# cs3_redraw.net
KiCad netlist of a schematic drawn in EAGLE
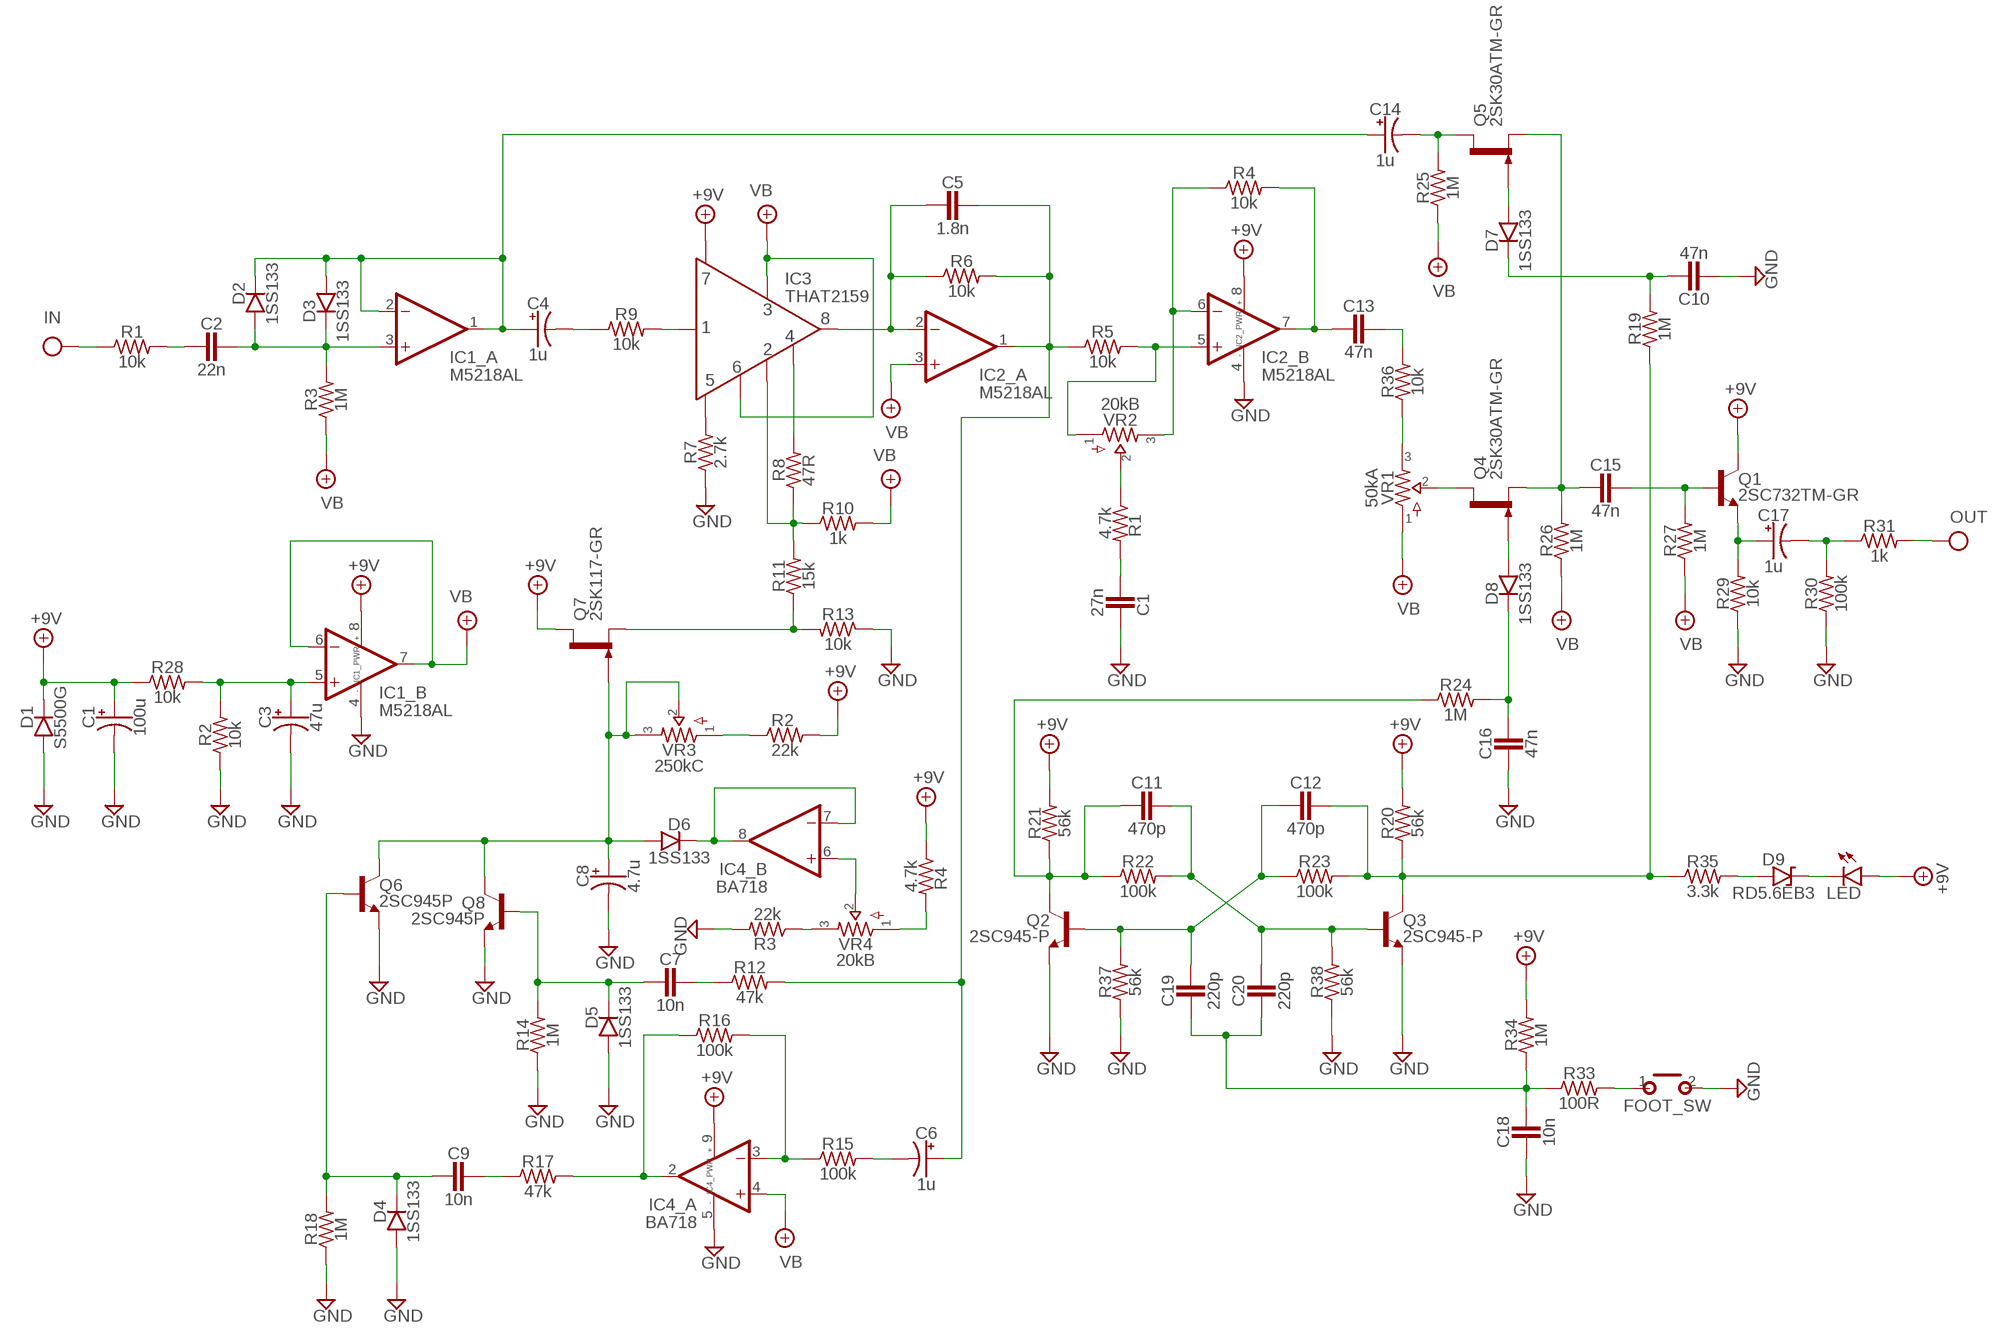
[diagram p0: schematic, sheet 1]

(export (version "E")
  (design (tool "Eeschema 10.0.6"))
  (components
    (comp (ref "C1")
      (value "100u")
      (footprint "eagle-import:040_020")
      (libsource (lib "eagle-import") (part "0400"))
    )
    (comp (ref "C1 ")
      (value "27n")
      (footprint "eagle-import:BOX_SMALL")
      (libsource (lib "eagle-import") (part "CER/FILMBOX.1"))
    )
    (comp (ref "C2")
      (value "22n")
      (footprint "eagle-import:BOX_SMALL")
      (libsource (lib "eagle-import") (part "CER/FILMBOX.1"))
    )
    (comp (ref "C3")
      (value "47u")
      (footprint "eagle-import:040_020")
      (libsource (lib "eagle-import") (part "0400"))
    )
    (comp (ref "C4")
      (value "1u")
      (footprint "eagle-import:040_020")
      (libsource (lib "eagle-import") (part "0400"))
    )
    (comp (ref "C5")
      (value "1.8n")
      (footprint "eagle-import:BOX_SMALL")
      (libsource (lib "eagle-import") (part "CER/FILMBOX.1"))
    )
    (comp (ref "C6")
      (value "1u")
      (footprint "eagle-import:040_020")
      (libsource (lib "eagle-import") (part "0400"))
    )
    (comp (ref "C7")
      (value "10n")
      (footprint "eagle-import:BOX_SMALL")
      (libsource (lib "eagle-import") (part "CER/FILMBOX.1"))
    )
    (comp (ref "C8")
      (value "4.7u")
      (footprint "eagle-import:040_020")
      (libsource (lib "eagle-import") (part "0400"))
    )
    (comp (ref "C9")
      (value "10n")
      (footprint "eagle-import:BOX_SMALL")
      (libsource (lib "eagle-import") (part "CER/FILMBOX.1"))
    )
    (comp (ref "C10")
      (value "47n")
      (footprint "eagle-import:BOX_SMALL")
      (libsource (lib "eagle-import") (part "CER/FILMBOX.1"))
    )
    (comp (ref "C11")
      (value "470p")
      (footprint "eagle-import:BOX_SMALL")
      (libsource (lib "eagle-import") (part "CER/FILMBOX.1"))
    )
    (comp (ref "C12")
      (value "470p")
      (footprint "eagle-import:BOX_SMALL")
      (libsource (lib "eagle-import") (part "CER/FILMBOX.1"))
    )
    (comp (ref "C13")
      (value "47n")
      (footprint "eagle-import:BOX_SMALL")
      (libsource (lib "eagle-import") (part "CER/FILMBOX.1"))
    )
    (comp (ref "C14")
      (value "1u")
      (footprint "eagle-import:040_020")
      (libsource (lib "eagle-import") (part "0400"))
    )
    (comp (ref "C15")
      (value "47n")
      (footprint "eagle-import:BOX_SMALL")
      (libsource (lib "eagle-import") (part "CER/FILMBOX.1"))
    )
    (comp (ref "C16")
      (value "47n")
      (footprint "eagle-import:BOX_SMALL")
      (libsource (lib "eagle-import") (part "CER/FILMBOX.1"))
    )
    (comp (ref "C17")
      (value "1u")
      (footprint "eagle-import:040_020")
      (libsource (lib "eagle-import") (part "0400"))
    )
    (comp (ref "C18")
      (value "10n")
      (footprint "eagle-import:BOX_SMALL")
      (libsource (lib "eagle-import") (part "CER/FILMBOX.1"))
    )
    (comp (ref "C19")
      (value "220p")
      (footprint "eagle-import:BOX_SMALL")
      (libsource (lib "eagle-import") (part "CER/FILMBOX.1"))
    )
    (comp (ref "C20")
      (value "220p")
      (footprint "eagle-import:BOX_SMALL")
      (libsource (lib "eagle-import") (part "CER/FILMBOX.1"))
    )
    (comp (ref "D1")
      (value "S5500G")
      (footprint "eagle-import:DO35-2")
      (libsource (lib "eagle-import") (part "DO35.2"))
    )
    (comp (ref "D2")
      (value "1SS133")
      (footprint "eagle-import:DO35-2")
      (libsource (lib "eagle-import") (part "DO35.2"))
    )
    (comp (ref "D3")
      (value "1SS133")
      (footprint "eagle-import:DO35-2")
      (libsource (lib "eagle-import") (part "DO35.2"))
    )
    (comp (ref "D4")
      (value "1SS133")
      (footprint "eagle-import:DO35-2")
      (libsource (lib "eagle-import") (part "DO35.2"))
    )
    (comp (ref "D5")
      (value "1SS133")
      (footprint "eagle-import:DO35-2")
      (libsource (lib "eagle-import") (part "DO35.2"))
    )
    (comp (ref "D6")
      (value "1SS133")
      (footprint "eagle-import:DO35-2")
      (libsource (lib "eagle-import") (part "DO35.2"))
    )
    (comp (ref "D7")
      (value "1SS133")
      (footprint "eagle-import:DO35-2")
      (libsource (lib "eagle-import") (part "DO35.2"))
    )
    (comp (ref "D8")
      (value "1SS133")
      (footprint "eagle-import:DO35-2")
      (libsource (lib "eagle-import") (part "DO35.2"))
    )
    (comp (ref "D9")
      (value "RD5.6EB3")
      (footprint "eagle-import:DO41-2")
      (libsource (lib "eagle-import") (part "ZENER.2"))
    )
    (comp (ref "FOOT_SW")
      (value "MOMENTARY")
      (footprint "eagle-import:SPST")
      (libsource (lib "eagle-import") (part "MOMENTARY"))
    )
    (comp (ref "IC1")
      (value "M5218AL")
      (footprint "eagle-import:DIL0")
      (libsource (lib "eagle-import") (part "DUALTH"))
    )
    (comp (ref "IC2")
      (value "M5218AL")
      (footprint "eagle-import:DIL0")
      (libsource (lib "eagle-import") (part "DUALTH"))
    )
    (comp (ref "IC3")
      (value "THAT2159")
      (footprint "eagle-import:SIL8")
      (libsource (lib "eagle-import") (part "THAT2181C"))
    )
    (comp (ref "IC4")
      (value "BA718")
      (footprint "eagle-import:SIL09")
      (libsource (lib "eagle-import") (part "DUAL"))
    )
    (comp (ref "LED")
      (value "LED")
      (footprint "eagle-import:3MM_D")
      (libsource (lib "eagle-import") (part "LED"))
    )
    (comp (ref "Q1")
      (value "2SC732TM-GR")
      (footprint "eagle-import:TO92-")
      (libsource (lib "eagle-import") (part "2N3904"))
    )
    (comp (ref "Q2")
      (value "2SC945-P")
      (footprint "eagle-import:TO92-")
      (libsource (lib "eagle-import") (part "2SC828A"))
    )
    (comp (ref "Q3")
      (value "2SC945-P")
      (footprint "eagle-import:TO92-")
      (libsource (lib "eagle-import") (part "2SC828A"))
    )
    (comp (ref "Q4")
      (value "2SK30ATM-GR")
      (footprint "eagle-import:TO92-")
      (libsource (lib "eagle-import") (part "2N5457"))
    )
    (comp (ref "Q5")
      (value "2SK30ATM-GR")
      (footprint "eagle-import:TO92-")
      (libsource (lib "eagle-import") (part "2N5457"))
    )
    (comp (ref "Q6")
      (value "2SC945P")
      (footprint "eagle-import:TO92-")
      (libsource (lib "eagle-import") (part "2N3904"))
    )
    (comp (ref "Q7")
      (value "2SK117-GR")
      (footprint "eagle-import:TO92-")
      (libsource (lib "eagle-import") (part "2N5457"))
    )
    (comp (ref "Q8")
      (value "2SC945P")
      (footprint "eagle-import:TO92-")
      (libsource (lib "eagle-import") (part "2N3904"))
    )
    (comp (ref "R1")
      (value "10k")
      (footprint "eagle-import:R0207_3")
      (libsource (lib "eagle-import") (part "R_.3B"))
    )
    (comp (ref "R1 ")
      (value "4.7k")
      (footprint "eagle-import:R0207_3")
      (libsource (lib "eagle-import") (part "R_.3B"))
    )
    (comp (ref "R2")
      (value "10k")
      (footprint "eagle-import:R0207_3")
      (libsource (lib "eagle-import") (part "R_.3B"))
    )
    (comp (ref "R2 ")
      (value "22k")
      (footprint "eagle-import:R0207_3")
      (libsource (lib "eagle-import") (part "R_.3B"))
    )
    (comp (ref "R3")
      (value "1M")
      (footprint "eagle-import:R0207_3")
      (libsource (lib "eagle-import") (part "R_.3B"))
    )
    (comp (ref "R3 ")
      (value "22k")
      (footprint "eagle-import:R0207_3")
      (libsource (lib "eagle-import") (part "R_.3B"))
    )
    (comp (ref "R4")
      (value "10k")
      (footprint "eagle-import:R0207_3")
      (libsource (lib "eagle-import") (part "R_.3B"))
    )
    (comp (ref "R4 ")
      (value "4.7k")
      (footprint "eagle-import:R0207_3")
      (libsource (lib "eagle-import") (part "R_.3B"))
    )
    (comp (ref "R5")
      (value "10k")
      (footprint "eagle-import:R0207_3")
      (libsource (lib "eagle-import") (part "R_.3B"))
    )
    (comp (ref "R6")
      (value "10k")
      (footprint "eagle-import:R0207_3")
      (libsource (lib "eagle-import") (part "R_.3B"))
    )
    (comp (ref "R7")
      (value "2.7k")
      (footprint "eagle-import:R0207_3")
      (libsource (lib "eagle-import") (part "R_.3B"))
    )
    (comp (ref "R8")
      (value "47R")
      (footprint "eagle-import:R0207_3")
      (libsource (lib "eagle-import") (part "R_.3B"))
    )
    (comp (ref "R9")
      (value "10k")
      (footprint "eagle-import:R0207_3")
      (libsource (lib "eagle-import") (part "R_.3B"))
    )
    (comp (ref "R10")
      (value "1k")
      (footprint "eagle-import:R0207_3")
      (libsource (lib "eagle-import") (part "R_.3B"))
    )
    (comp (ref "R11")
      (value "15k")
      (footprint "eagle-import:R0207_3")
      (libsource (lib "eagle-import") (part "R_.3B"))
    )
    (comp (ref "R12")
      (value "47k")
      (footprint "eagle-import:R0207_3")
      (libsource (lib "eagle-import") (part "R_.3B"))
    )
    (comp (ref "R13")
      (value "10k")
      (footprint "eagle-import:R0207_3")
      (libsource (lib "eagle-import") (part "R_.3B"))
    )
    (comp (ref "R14")
      (value "1M")
      (footprint "eagle-import:R0207_3")
      (libsource (lib "eagle-import") (part "R_.3B"))
    )
    (comp (ref "R15")
      (value "100k")
      (footprint "eagle-import:R0207_3")
      (libsource (lib "eagle-import") (part "R_.3B"))
    )
    (comp (ref "R16")
      (value "100k")
      (footprint "eagle-import:R0207_3")
      (libsource (lib "eagle-import") (part "R_.3B"))
    )
    (comp (ref "R17")
      (value "47k")
      (footprint "eagle-import:R0207_3")
      (libsource (lib "eagle-import") (part "R_.3B"))
    )
    (comp (ref "R18")
      (value "1M")
      (footprint "eagle-import:R0207_3")
      (libsource (lib "eagle-import") (part "R_.3B"))
    )
    (comp (ref "R19")
      (value "1M")
      (footprint "eagle-import:R0207_3")
      (libsource (lib "eagle-import") (part "R_.3B"))
    )
    (comp (ref "R20")
      (value "56k")
      (footprint "eagle-import:R0207_3")
      (libsource (lib "eagle-import") (part "R_.3B"))
    )
    (comp (ref "R21")
      (value "56k")
      (footprint "eagle-import:R0207_3")
      (libsource (lib "eagle-import") (part "R_.3B"))
    )
    (comp (ref "R22")
      (value "100k")
      (footprint "eagle-import:R0207_3")
      (libsource (lib "eagle-import") (part "R_.3B"))
    )
    (comp (ref "R23")
      (value "100k")
      (footprint "eagle-import:R0207_3")
      (libsource (lib "eagle-import") (part "R_.3B"))
    )
    (comp (ref "R24")
      (value "1M")
      (footprint "eagle-import:R0207_3")
      (libsource (lib "eagle-import") (part "R_.3B"))
    )
    (comp (ref "R25")
      (value "1M")
      (footprint "eagle-import:R0207_3")
      (libsource (lib "eagle-import") (part "R_.3B"))
    )
    (comp (ref "R26")
      (value "1M")
      (footprint "eagle-import:R0207_3")
      (libsource (lib "eagle-import") (part "R_.3B"))
    )
    (comp (ref "R27")
      (value "1M")
      (footprint "eagle-import:R0207_3")
      (libsource (lib "eagle-import") (part "R_.3B"))
    )
    (comp (ref "R28")
      (value "10k")
      (footprint "eagle-import:R0207_3")
      (libsource (lib "eagle-import") (part "R_.3B"))
    )
    (comp (ref "R29")
      (value "10k")
      (footprint "eagle-import:R0207_3")
      (libsource (lib "eagle-import") (part "R_.3B"))
    )
    (comp (ref "R30")
      (value "100k")
      (footprint "eagle-import:R0207_3")
      (libsource (lib "eagle-import") (part "R_.3B"))
    )
    (comp (ref "R31")
      (value "1k")
      (footprint "eagle-import:R0207_3")
      (libsource (lib "eagle-import") (part "R_.3B"))
    )
    (comp (ref "R33")
      (value "100R")
      (footprint "eagle-import:R0207_3")
      (libsource (lib "eagle-import") (part "R_.3B"))
    )
    (comp (ref "R34")
      (value "1M")
      (footprint "eagle-import:R0207_3")
      (libsource (lib "eagle-import") (part "R_.3B"))
    )
    (comp (ref "R35")
      (value "3.3k")
      (footprint "eagle-import:R0207_3")
      (libsource (lib "eagle-import") (part "R_.3B"))
    )
    (comp (ref "R36")
      (value "10k")
      (footprint "eagle-import:R0207_3")
      (libsource (lib "eagle-import") (part "R_.3B"))
    )
    (comp (ref "R37")
      (value "56k")
      (footprint "eagle-import:R0207_3")
      (libsource (lib "eagle-import") (part "R_.3B"))
    )
    (comp (ref "R38")
      (value "56k")
      (footprint "eagle-import:R0207_3")
      (libsource (lib "eagle-import") (part "R_.3B"))
    )
    (comp (ref "VR1")
      (value "50kA")
      (footprint "eagle-import:16MM")
      (libsource (lib "eagle-import") (part "POTS16MM"))
    )
    (comp (ref "VR2")
      (value "20kB")
      (footprint "eagle-import:16MM")
      (libsource (lib "eagle-import") (part "POTS16MM"))
    )
    (comp (ref "VR3")
      (value "250kC")
      (footprint "eagle-import:16MM")
      (libsource (lib "eagle-import") (part "POTS16MM"))
    )
    (comp (ref "VR4")
      (value "20kB")
      (footprint "eagle-import:16MM")
      (libsource (lib "eagle-import") (part "POTS16MM"))
    )
  )
  (nets
    (net (code "1") (name "+9V") (class "Default")
      (node (ref "C1") (pin "+") (pinfunction "+_+") (pintype "passive"))
      (node (ref "D1") (pin "C") (pinfunction "C_C") (pintype "passive"))
      (node (ref "IC1") (pin "8") (pinfunction "V+_8") (pintype "power_in"))
      (node (ref "IC2") (pin "8") (pinfunction "V+_8") (pintype "power_in"))
      (node (ref "IC3") (pin "7") (pinfunction "P$7_7") (pintype "bidirectional"))
      (node (ref "IC4") (pin "9") (pinfunction "V+_9") (pintype "power_in"))
      (node (ref "LED") (pin "ANODE") (pinfunction "A_ANODE") (pintype "passive"))
      (node (ref "Q1") (pin "1") (pinfunction "C_1") (pintype "passive"))
      (node (ref "Q7") (pin "3") (pinfunction "D_3") (pintype "passive"))
      (node (ref "R20") (pin "2") (pinfunction "2_2") (pintype "passive"))
      (node (ref "R21") (pin "2") (pinfunction "2_2") (pintype "passive"))
      (node (ref "R28") (pin "1") (pinfunction "1_1") (pintype "passive"))
      (node (ref "R2 ") (pin "2") (pinfunction "2_2") (pintype "passive"))
      (node (ref "R34") (pin "2") (pinfunction "2_2") (pintype "passive"))
      (node (ref "R4 ") (pin "1") (pinfunction "1_1") (pintype "passive"))
    )
    (net (code "2") (name "GND") (class "Default")
      (node (ref "C1") (pin "-") (pinfunction "-_-") (pintype "passive"))
      (node (ref "C10") (pin "2") (pinfunction "2_2") (pintype "passive"))
      (node (ref "C16") (pin "2") (pinfunction "2_2") (pintype "passive"))
      (node (ref "C18") (pin "2") (pinfunction "2_2") (pintype "passive"))
      (node (ref "C1 ") (pin "2") (pinfunction "2_2") (pintype "passive"))
      (node (ref "C3") (pin "-") (pinfunction "-_-") (pintype "passive"))
      (node (ref "C8") (pin "-") (pinfunction "-_-") (pintype "passive"))
      (node (ref "D1") (pin "A") (pinfunction "A_A") (pintype "passive"))
      (node (ref "D4") (pin "A") (pinfunction "A_A") (pintype "passive"))
      (node (ref "D5") (pin "A") (pinfunction "A_A") (pintype "passive"))
      (node (ref "FOOT_SW") (pin "2") (pinfunction "S_2") (pintype "passive"))
      (node (ref "IC1") (pin "4") (pinfunction "V-_4") (pintype "power_in"))
      (node (ref "IC2") (pin "4") (pinfunction "V-_4") (pintype "power_in"))
      (node (ref "IC4") (pin "5") (pinfunction "V-_5") (pintype "power_in"))
      (node (ref "Q2") (pin "3") (pinfunction "E_3") (pintype "passive"))
      (node (ref "Q3") (pin "3") (pinfunction "E_3") (pintype "passive"))
      (node (ref "Q6") (pin "3") (pinfunction "E_3") (pintype "passive"))
      (node (ref "Q8") (pin "3") (pinfunction "E_3") (pintype "passive"))
      (node (ref "R13") (pin "1") (pinfunction "1_1") (pintype "passive"))
      (node (ref "R14") (pin "1") (pinfunction "1_1") (pintype "passive"))
      (node (ref "R18") (pin "1") (pinfunction "1_1") (pintype "passive"))
      (node (ref "R2") (pin "1") (pinfunction "1_1") (pintype "passive"))
      (node (ref "R29") (pin "1") (pinfunction "1_1") (pintype "passive"))
      (node (ref "R30") (pin "1") (pinfunction "1_1") (pintype "passive"))
      (node (ref "R37") (pin "1") (pinfunction "1_1") (pintype "passive"))
      (node (ref "R38") (pin "1") (pinfunction "1_1") (pintype "passive"))
      (node (ref "R3 ") (pin "2") (pinfunction "2_2") (pintype "passive"))
      (node (ref "R7") (pin "1") (pinfunction "1_1") (pintype "passive"))
    )
    (net (code "3") (name "IN") (class "Default")
      (node (ref "R1") (pin "1") (pinfunction "1_1") (pintype "passive"))
    )
    (net (code "4") (name "Net-(C1 -Pad1)") (class "Default")
      (node (ref "C1 ") (pin "1") (pinfunction "1_1") (pintype "passive"))
      (node (ref "R1 ") (pin "2") (pinfunction "2_2") (pintype "passive"))
    )
    (net (code "5") (name "Net-(C2-Pad2)") (class "Default")
      (node (ref "C2") (pin "2") (pinfunction "2_2") (pintype "passive"))
      (node (ref "R1") (pin "2") (pinfunction "2_2") (pintype "passive"))
    )
    (net (code "6") (name "Net-(C4-Pad-)") (class "Default")
      (node (ref "C4") (pin "-") (pinfunction "-_-") (pintype "passive"))
      (node (ref "R9") (pin "1") (pinfunction "1_1") (pintype "passive"))
    )
    (net (code "7") (name "Net-(C6-Pad-)") (class "Default")
      (node (ref "C6") (pin "-") (pinfunction "-_-") (pintype "passive"))
      (node (ref "R15") (pin "2") (pinfunction "2_2") (pintype "passive"))
    )
    (net (code "8") (name "Net-(C7-Pad1)") (class "Default")
      (node (ref "C7") (pin "1") (pinfunction "1_1") (pintype "passive"))
      (node (ref "R12") (pin "1") (pinfunction "1_1") (pintype "passive"))
    )
    (net (code "9") (name "Net-(C9-Pad1)") (class "Default")
      (node (ref "C9") (pin "1") (pinfunction "1_1") (pintype "passive"))
      (node (ref "R17") (pin "1") (pinfunction "1_1") (pintype "passive"))
    )
    (net (code "10") (name "Net-(C10-Pad1)") (class "Default")
      (node (ref "C10") (pin "1") (pinfunction "1_1") (pintype "passive"))
      (node (ref "D7") (pin "C") (pinfunction "C_C") (pintype "passive"))
      (node (ref "R19") (pin "2") (pinfunction "2_2") (pintype "passive"))
    )
    (net (code "11") (name "Net-(C13-Pad1)") (class "Default")
      (node (ref "C13") (pin "1") (pinfunction "1_1") (pintype "passive"))
      (node (ref "R36") (pin "2") (pinfunction "2_2") (pintype "passive"))
    )
    (net (code "12") (name "Net-(C16-Pad1)") (class "Default")
      (node (ref "C16") (pin "1") (pinfunction "1_1") (pintype "passive"))
      (node (ref "D8") (pin "C") (pinfunction "C_C") (pintype "passive"))
      (node (ref "R24") (pin "2") (pinfunction "2_2") (pintype "passive"))
    )
    (net (code "13") (name "Net-(C17-Pad-)") (class "Default")
      (node (ref "C17") (pin "-") (pinfunction "-_-") (pintype "passive"))
      (node (ref "R30") (pin "2") (pinfunction "2_2") (pintype "passive"))
      (node (ref "R31") (pin "1") (pinfunction "1_1") (pintype "passive"))
    )
    (net (code "14") (name "Net-(C18-Pad1)") (class "Default")
      (node (ref "C18") (pin "1") (pinfunction "1_1") (pintype "passive"))
      (node (ref "C19") (pin "2") (pinfunction "2_2") (pintype "passive"))
      (node (ref "C20") (pin "2") (pinfunction "2_2") (pintype "passive"))
      (node (ref "R33") (pin "1") (pinfunction "1_1") (pintype "passive"))
      (node (ref "R34") (pin "1") (pinfunction "1_1") (pintype "passive"))
    )
    (net (code "15") (name "Net-(D9-PadA)") (class "Default")
      (node (ref "D9") (pin "A") (pinfunction "A_A") (pintype "passive"))
      (node (ref "R35") (pin "2") (pinfunction "2_2") (pintype "passive"))
    )
    (net (code "16") (name "Net-(FOOT_SW-P)") (class "Default")
      (node (ref "FOOT_SW") (pin "1") (pinfunction "P_1") (pintype "passive"))
      (node (ref "R33") (pin "2") (pinfunction "2_2") (pintype "passive"))
    )
    (net (code "17") (name "Net-(IC1A-+IN)") (class "Default")
      (node (ref "C2") (pin "1") (pinfunction "1_1") (pintype "passive"))
      (node (ref "D2") (pin "A") (pinfunction "A_A") (pintype "passive"))
      (node (ref "D3") (pin "C") (pinfunction "C_C") (pintype "passive"))
      (node (ref "IC1") (pin "3") (pinfunction "+IN_3") (pintype "input"))
      (node (ref "R3") (pin "2") (pinfunction "2_2") (pintype "passive"))
    )
    (net (code "18") (name "Net-(IC1A--IN)") (class "Default")
      (node (ref "C14") (pin "+") (pinfunction "+_+") (pintype "passive"))
      (node (ref "C4") (pin "+") (pinfunction "+_+") (pintype "passive"))
      (node (ref "D2") (pin "C") (pinfunction "C_C") (pintype "passive"))
      (node (ref "D3") (pin "A") (pinfunction "A_A") (pintype "passive"))
      (node (ref "IC1") (pin "1") (pinfunction "OUT_1") (pintype "output"))
      (node (ref "IC1") (pin "2") (pinfunction "-IN_2") (pintype "input"))
    )
    (net (code "19") (name "Net-(IC1B-+IN)") (class "Default")
      (node (ref "C3") (pin "+") (pinfunction "+_+") (pintype "passive"))
      (node (ref "IC1") (pin "5") (pinfunction "+IN_5") (pintype "input"))
      (node (ref "R2") (pin "2") (pinfunction "2_2") (pintype "passive"))
      (node (ref "R28") (pin "2") (pinfunction "2_2") (pintype "passive"))
    )
    (net (code "20") (name "Net-(IC2A--IN)") (class "Default")
      (node (ref "C5") (pin "2") (pinfunction "2_2") (pintype "passive"))
      (node (ref "IC2") (pin "2") (pinfunction "-IN_2") (pintype "input"))
      (node (ref "IC3") (pin "8") (pinfunction "P$8_8") (pintype "bidirectional"))
      (node (ref "R6") (pin "1") (pinfunction "1_1") (pintype "passive"))
    )
    (net (code "21") (name "Net-(IC2A-OUT)") (class "Default")
      (node (ref "C5") (pin "1") (pinfunction "1_1") (pintype "passive"))
      (node (ref "C6") (pin "+") (pinfunction "+_+") (pintype "passive"))
      (node (ref "IC2") (pin "1") (pinfunction "OUT_1") (pintype "output"))
      (node (ref "R12") (pin "2") (pinfunction "2_2") (pintype "passive"))
      (node (ref "R5") (pin "1") (pinfunction "1_1") (pintype "passive"))
      (node (ref "R6") (pin "2") (pinfunction "2_2") (pintype "passive"))
    )
    (net (code "22") (name "Net-(IC2B-+IN)") (class "Default")
      (node (ref "IC2") (pin "5") (pinfunction "+IN_5") (pintype "input"))
      (node (ref "R5") (pin "2") (pinfunction "2_2") (pintype "passive"))
      (node (ref "VR2") (pin "1") (pinfunction "1_1") (pintype "passive"))
    )
    (net (code "23") (name "Net-(IC2B--IN)") (class "Default")
      (node (ref "IC2") (pin "6") (pinfunction "-IN_6") (pintype "input"))
      (node (ref "R4") (pin "1") (pinfunction "1_1") (pintype "passive"))
      (node (ref "VR2") (pin "3") (pinfunction "3_3") (pintype "passive"))
    )
    (net (code "24") (name "Net-(IC2B-OUT)") (class "Default")
      (node (ref "C13") (pin "2") (pinfunction "2_2") (pintype "passive"))
      (node (ref "IC2") (pin "7") (pinfunction "OUT_7") (pintype "output"))
      (node (ref "R4") (pin "2") (pinfunction "2_2") (pintype "passive"))
    )
    (net (code "25") (name "Net-(IC3-P$1)") (class "Default")
      (node (ref "IC3") (pin "1") (pinfunction "P$1_1") (pintype "bidirectional"))
      (node (ref "R9") (pin "2") (pinfunction "2_2") (pintype "passive"))
    )
    (net (code "26") (name "Net-(IC3-P$2)") (class "Default")
      (node (ref "IC3") (pin "2") (pinfunction "P$2_2") (pintype "bidirectional"))
      (node (ref "R10") (pin "1") (pinfunction "1_1") (pintype "passive"))
      (node (ref "R11") (pin "2") (pinfunction "2_2") (pintype "passive"))
      (node (ref "R8") (pin "1") (pinfunction "1_1") (pintype "passive"))
    )
    (net (code "27") (name "Net-(IC3-P$4)") (class "Default")
      (node (ref "IC3") (pin "4") (pinfunction "P$4_4") (pintype "bidirectional"))
      (node (ref "R8") (pin "2") (pinfunction "2_2") (pintype "passive"))
    )
    (net (code "28") (name "Net-(IC3-P$5)") (class "Default")
      (node (ref "IC3") (pin "5") (pinfunction "P$5_5") (pintype "bidirectional"))
      (node (ref "R7") (pin "2") (pinfunction "2_2") (pintype "passive"))
    )
    (net (code "29") (name "Net-(IC4A--IN)") (class "Default")
      (node (ref "IC4") (pin "3") (pinfunction "-IN_3") (pintype "input"))
      (node (ref "R15") (pin "1") (pinfunction "1_1") (pintype "passive"))
      (node (ref "R16") (pin "2") (pinfunction "2_2") (pintype "passive"))
    )
    (net (code "30") (name "Net-(IC4A-OUT)") (class "Default")
      (node (ref "IC4") (pin "2") (pinfunction "OUT_2") (pintype "output"))
      (node (ref "R16") (pin "1") (pinfunction "1_1") (pintype "passive"))
      (node (ref "R17") (pin "2") (pinfunction "2_2") (pintype "passive"))
    )
    (net (code "31") (name "Net-(IC4B-+IN)") (class "Default")
      (node (ref "IC4") (pin "6") (pinfunction "+IN_6") (pintype "input"))
      (node (ref "VR4") (pin "2") (pinfunction "2_2") (pintype "passive"))
    )
    (net (code "32") (name "Net-(IC4B--IN)") (class "Default")
      (node (ref "D6") (pin "C") (pinfunction "C_C") (pintype "passive"))
      (node (ref "IC4") (pin "7") (pinfunction "-IN_7") (pintype "input"))
      (node (ref "IC4") (pin "8") (pinfunction "OUT_8") (pintype "output"))
    )
    (net (code "33") (name "Net-(LED-C)") (class "Default")
      (node (ref "D9") (pin "C") (pinfunction "C_C") (pintype "passive"))
      (node (ref "LED") (pin "P$1") (pinfunction "C_P$1") (pintype "passive"))
    )
    (net (code "34") (name "Net-(Q1-B)") (class "Default")
      (node (ref "C15") (pin "1") (pinfunction "1_1") (pintype "passive"))
      (node (ref "Q1") (pin "2") (pinfunction "B_2") (pintype "passive"))
      (node (ref "R27") (pin "2") (pinfunction "2_2") (pintype "passive"))
    )
    (net (code "35") (name "Net-(Q1-E)") (class "Default")
      (node (ref "C17") (pin "+") (pinfunction "+_+") (pintype "passive"))
      (node (ref "Q1") (pin "3") (pinfunction "E_3") (pintype "passive"))
      (node (ref "R29") (pin "2") (pinfunction "2_2") (pintype "passive"))
    )
    (net (code "36") (name "Net-(Q2-B)") (class "Default")
      (node (ref "C12") (pin "2") (pinfunction "2_2") (pintype "passive"))
      (node (ref "C19") (pin "1") (pinfunction "1_1") (pintype "passive"))
      (node (ref "Q2") (pin "1") (pinfunction "B_1") (pintype "passive"))
      (node (ref "R23") (pin "1") (pinfunction "1_1") (pintype "passive"))
      (node (ref "R37") (pin "2") (pinfunction "2_2") (pintype "passive"))
    )
    (net (code "37") (name "Net-(Q2-C)") (class "Default")
      (node (ref "C11") (pin "2") (pinfunction "2_2") (pintype "passive"))
      (node (ref "Q2") (pin "2") (pinfunction "C_2") (pintype "passive"))
      (node (ref "R21") (pin "1") (pinfunction "1_1") (pintype "passive"))
      (node (ref "R22") (pin "1") (pinfunction "1_1") (pintype "passive"))
      (node (ref "R24") (pin "1") (pinfunction "1_1") (pintype "passive"))
    )
    (net (code "38") (name "Net-(Q3-B)") (class "Default")
      (node (ref "C11") (pin "1") (pinfunction "1_1") (pintype "passive"))
      (node (ref "C20") (pin "1") (pinfunction "1_1") (pintype "passive"))
      (node (ref "Q3") (pin "1") (pinfunction "B_1") (pintype "passive"))
      (node (ref "R22") (pin "2") (pinfunction "2_2") (pintype "passive"))
      (node (ref "R38") (pin "2") (pinfunction "2_2") (pintype "passive"))
    )
    (net (code "39") (name "Net-(Q3-C)") (class "Default")
      (node (ref "C12") (pin "1") (pinfunction "1_1") (pintype "passive"))
      (node (ref "Q3") (pin "2") (pinfunction "C_2") (pintype "passive"))
      (node (ref "R19") (pin "1") (pinfunction "1_1") (pintype "passive"))
      (node (ref "R20") (pin "1") (pinfunction "1_1") (pintype "passive"))
      (node (ref "R23") (pin "2") (pinfunction "2_2") (pintype "passive"))
      (node (ref "R35") (pin "1") (pinfunction "1_1") (pintype "passive"))
    )
    (net (code "40") (name "Net-(Q4-D)") (class "Default")
      (node (ref "Q4") (pin "3") (pinfunction "D_3") (pintype "passive"))
      (node (ref "VR1") (pin "2") (pinfunction "2_2") (pintype "passive"))
    )
    (net (code "41") (name "Net-(Q4-G)") (class "Default")
      (node (ref "D8") (pin "A") (pinfunction "A_A") (pintype "passive"))
      (node (ref "Q4") (pin "1") (pinfunction "G_1") (pintype "passive"))
    )
    (net (code "42") (name "Net-(Q4-S)") (class "Default")
      (node (ref "C15") (pin "2") (pinfunction "2_2") (pintype "passive"))
      (node (ref "Q4") (pin "2") (pinfunction "S_2") (pintype "passive"))
      (node (ref "Q5") (pin "2") (pinfunction "S_2") (pintype "passive"))
      (node (ref "R26") (pin "2") (pinfunction "2_2") (pintype "passive"))
    )
    (net (code "43") (name "Net-(Q5-D)") (class "Default")
      (node (ref "C14") (pin "-") (pinfunction "-_-") (pintype "passive"))
      (node (ref "Q5") (pin "3") (pinfunction "D_3") (pintype "passive"))
      (node (ref "R25") (pin "2") (pinfunction "2_2") (pintype "passive"))
    )
    (net (code "44") (name "Net-(Q5-G)") (class "Default")
      (node (ref "D7") (pin "A") (pinfunction "A_A") (pintype "passive"))
      (node (ref "Q5") (pin "1") (pinfunction "G_1") (pintype "passive"))
    )
    (net (code "45") (name "Net-(Q6-B)") (class "Default")
      (node (ref "C9") (pin "2") (pinfunction "2_2") (pintype "passive"))
      (node (ref "D4") (pin "C") (pinfunction "C_C") (pintype "passive"))
      (node (ref "Q6") (pin "2") (pinfunction "B_2") (pintype "passive"))
      (node (ref "R18") (pin "2") (pinfunction "2_2") (pintype "passive"))
    )
    (net (code "46") (name "Net-(Q6-C)") (class "Default")
      (node (ref "C8") (pin "+") (pinfunction "+_+") (pintype "passive"))
      (node (ref "D6") (pin "A") (pinfunction "A_A") (pintype "passive"))
      (node (ref "Q6") (pin "1") (pinfunction "C_1") (pintype "passive"))
      (node (ref "Q7") (pin "1") (pinfunction "G_1") (pintype "passive"))
      (node (ref "Q8") (pin "1") (pinfunction "C_1") (pintype "passive"))
      (node (ref "VR3") (pin "2") (pinfunction "2_2") (pintype "passive"))
      (node (ref "VR3") (pin "3") (pinfunction "3_3") (pintype "passive"))
    )
    (net (code "47") (name "Net-(Q7-S)") (class "Default")
      (node (ref "Q7") (pin "2") (pinfunction "S_2") (pintype "passive"))
      (node (ref "R11") (pin "1") (pinfunction "1_1") (pintype "passive"))
      (node (ref "R13") (pin "2") (pinfunction "2_2") (pintype "passive"))
    )
    (net (code "48") (name "Net-(Q8-B)") (class "Default")
      (node (ref "C7") (pin "2") (pinfunction "2_2") (pintype "passive"))
      (node (ref "D5") (pin "C") (pinfunction "C_C") (pintype "passive"))
      (node (ref "Q8") (pin "2") (pinfunction "B_2") (pintype "passive"))
      (node (ref "R14") (pin "2") (pinfunction "2_2") (pintype "passive"))
    )
    (net (code "49") (name "Net-(R1 -Pad1)") (class "Default")
      (node (ref "R1 ") (pin "1") (pinfunction "1_1") (pintype "passive"))
      (node (ref "VR2") (pin "2") (pinfunction "2_2") (pintype "passive"))
    )
    (net (code "50") (name "Net-(R2 -Pad1)") (class "Default")
      (node (ref "R2 ") (pin "1") (pinfunction "1_1") (pintype "passive"))
      (node (ref "VR3") (pin "1") (pinfunction "1_1") (pintype "passive"))
    )
    (net (code "51") (name "Net-(R3 -Pad1)") (class "Default")
      (node (ref "R3 ") (pin "1") (pinfunction "1_1") (pintype "passive"))
      (node (ref "VR4") (pin "3") (pinfunction "3_3") (pintype "passive"))
    )
    (net (code "52") (name "Net-(R4 -Pad2)") (class "Default")
      (node (ref "R4 ") (pin "2") (pinfunction "2_2") (pintype "passive"))
      (node (ref "VR4") (pin "1") (pinfunction "1_1") (pintype "passive"))
    )
    (net (code "53") (name "Net-(R36-Pad1)") (class "Default")
      (node (ref "R36") (pin "1") (pinfunction "1_1") (pintype "passive"))
      (node (ref "VR1") (pin "3") (pinfunction "3_3") (pintype "passive"))
    )
    (net (code "54") (name "OUT") (class "Default")
      (node (ref "R31") (pin "2") (pinfunction "2_2") (pintype "passive"))
    )
    (net (code "55") (name "VB") (class "Default")
      (node (ref "IC1") (pin "6") (pinfunction "-IN_6") (pintype "input"))
      (node (ref "IC1") (pin "7") (pinfunction "OUT_7") (pintype "output"))
      (node (ref "IC2") (pin "3") (pinfunction "+IN_3") (pintype "input"))
      (node (ref "IC3") (pin "3") (pinfunction "P$3_3") (pintype "bidirectional"))
      (node (ref "IC3") (pin "6") (pinfunction "P$6_6") (pintype "bidirectional"))
      (node (ref "IC4") (pin "4") (pinfunction "+IN_4") (pintype "input"))
      (node (ref "R10") (pin "2") (pinfunction "2_2") (pintype "passive"))
      (node (ref "R25") (pin "1") (pinfunction "1_1") (pintype "passive"))
      (node (ref "R26") (pin "1") (pinfunction "1_1") (pintype "passive"))
      (node (ref "R27") (pin "1") (pinfunction "1_1") (pintype "passive"))
      (node (ref "R3") (pin "1") (pinfunction "1_1") (pintype "passive"))
      (node (ref "VR1") (pin "1") (pinfunction "1_1") (pintype "passive"))
    )
  )
)
